# version_1.net
KiCad netlist of a schematic drawn in Altium Designer
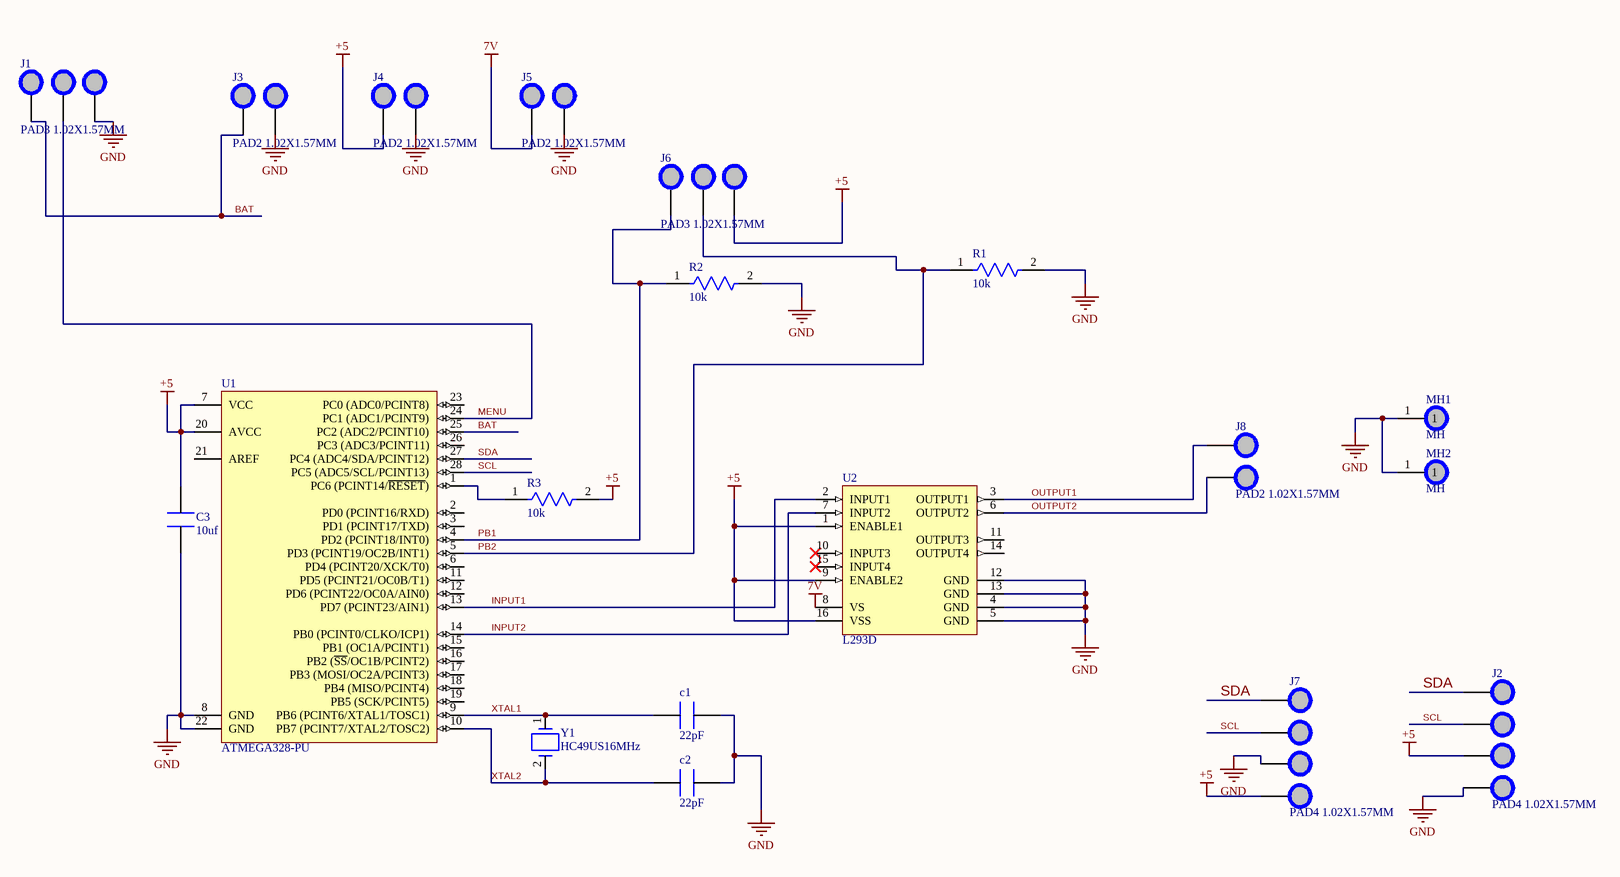
[diagram p0: version_1.SchDoc]

(export (version "E")
  (design (tool "Eeschema 10.0.6"))
  (components
    (comp (ref "c1")
      (value "22pF")
      (footprint "0805 22pf")
      (fields
        (field (name "MANUFACTURER") "KEMET")
        (field (name "MANUFACTURER PART NUMBER") "C0805C220J4HACTU")
      )
      (libsource (lib "Schlib1") (part "C0805C220J4HACTU"))
    )
    (comp (ref "c2")
      (value "22pF")
      (footprint "0805 22pf")
      (fields
        (field (name "MANUFACTURER") "KEMET")
        (field (name "MANUFACTURER PART NUMBER") "C0805C220J4HACTU")
      )
      (libsource (lib "Schlib1") (part "C0805C220J4HACTU"))
    )
    (comp (ref "C3")
      (value "10uf")
      (footprint "0805 cap")
      (fields
        (field (name "MANUFACTURER") "Samsung")
        (field (name "MANUFACTURER PART NUMBER") "CL21A106KOQNNNE")
        (field (name "TOLERANCE") "10%")
      )
      (libsource (lib "Schlib1") (part "CL21A106KOQNNNE"))
    )
    (comp (ref "J1")
      (value "PAD3 1.02X1.57MM")
      (footprint "PAD3 1.02X1.57MM")
      (libsource (lib "Schlib1") (part "PAD3 1.02X1.57MM"))
    )
    (comp (ref "J2")
      (value "PAD4 1.02X1.57MM")
      (footprint "PAD4 1.02X1.57MM")
      (libsource (lib "Schlib1") (part "PAD4 1.02X1.57MM"))
    )
    (comp (ref "J3")
      (value "PAD2 1.02X1.57MM")
      (footprint "PAD2 1.02X1.57MM")
      (libsource (lib "Schlib1") (part "PAD2 1.02X1.57MM"))
    )
    (comp (ref "J4")
      (value "PAD2 1.02X1.57MM")
      (footprint "PAD2 1.02X1.57MM")
      (libsource (lib "Schlib1") (part "PAD2 1.02X1.57MM"))
    )
    (comp (ref "J5")
      (value "PAD2 1.02X1.57MM")
      (footprint "PAD2 1.02X1.57MM")
      (libsource (lib "Schlib1") (part "PAD2 1.02X1.57MM"))
    )
    (comp (ref "J6")
      (value "PAD3 1.02X1.57MM")
      (footprint "PAD3 1.02X1.57MM")
      (libsource (lib "Schlib1") (part "PAD3 1.02X1.57MM"))
    )
    (comp (ref "J7")
      (value "PAD4 1.02X1.57MM")
      (footprint "PAD4 1.02X1.57MM")
      (libsource (lib "Schlib1") (part "PAD4 1.02X1.57MM"))
    )
    (comp (ref "J8")
      (value "PAD2 1.02X1.57MM")
      (footprint "PAD2 1.02X1.57MM")
      (libsource (lib "Schlib1") (part "PAD2 1.02X1.57MM"))
    )
    (comp (ref "MH1") (value "MH") (footprint "MH") (libsource (lib "Schlib1") (part "MH")))
    (comp (ref "MH2") (value "MH") (footprint "MH") (libsource (lib "Schlib1") (part "MH")))
    (comp (ref "R1")
      (value "10k")
      (footprint "0805 resistor")
      (description "Res Thick Film 0805 10K Ohm 1% 0.125W(1/8W) +/-100ppm/C Epoxy Pad SMD T/R")
      (fields
        (field (name "MANUFACTURER") "Yageo")
        (field (name "MANUFACTURER PART NUMBER") "RC0805FR-0710KL")
      )
      (libsource (lib "Schlib1") (part "RC0805FR-0710KL"))
    )
    (comp (ref "R2")
      (value "10k")
      (footprint "0805 resistor")
      (description "Res Thick Film 0805 10K Ohm 1% 0.125W(1/8W) +/-100ppm/C Epoxy Pad SMD T/R")
      (fields
        (field (name "MANUFACTURER") "Yageo")
        (field (name "MANUFACTURER PART NUMBER") "RC0805FR-0710KL")
      )
      (libsource (lib "Schlib1") (part "RC0805FR-0710KL"))
    )
    (comp (ref "R3")
      (value "10k")
      (footprint "0805 resistor")
      (description "Res Thick Film 0805 10K Ohm 1% 0.125W(1/8W) +/-100ppm/C Epoxy Pad SMD T/R")
      (fields
        (field (name "MANUFACTURER") "Yageo")
        (field (name "MANUFACTURER PART NUMBER") "RC0805FR-0710KL")
      )
      (libsource (lib "Schlib1") (part "RC0805FR-0710KL"))
    )
    (comp (ref "U1")
      (value "ATMEGA328-PU")
      (footprint "DIP28 7.62MM")
      (description "ATmega Series 32 kB Flash 2 kB SRAM 20 MHz 8-Bit Microcontroller - DIP-28")
      (fields (field (name "MANUFACTURER") "Microchip"))
      (libsource (lib "Schlib1") (part "ATMEGA328-PU"))
    )
    (comp (ref "U2")
      (value "L293D")
      (footprint "DIP16")
      (description "IC MOTOR DRIVER PAR 16-DIP")
      (fields (field (name "MANUFACTURER") "STMicroelectronics"))
      (libsource (lib "Schlib1") (part "L293D"))
    )
    (comp (ref "Y1")
      (value "HC49US16MHz")
      (footprint "HC49US16MHz")
      (fields
        (field (name "MANUFACTURER") "Citizen")
        (field (name "MANUFACTURER PART NUMBER") "HC49US16.384MABJ-UB")
      )
      (libsource (lib "Schlib1") (part "HC49US16.384MABJ-UB"))
    )
  )
  (nets
    (net (code "1") (name "+5") (class "Default")
      (node (ref "C3") (pin "2") (pinfunction "2_2") (pintype "passive"))
      (node (ref "J2") (pin "3") (pinfunction "3_3") (pintype "passive"))
      (node (ref "J4") (pin "1") (pinfunction "1_1") (pintype "passive"))
      (node (ref "J6") (pin "3") (pinfunction "3_3") (pintype "passive"))
      (node (ref "J7") (pin "4") (pinfunction "4_4") (pintype "passive"))
      (node (ref "R3") (pin "2") (pinfunction "2_2") (pintype "passive"))
      (node (ref "U1") (pin "20") (pinfunction "AVCC_20") (pintype "power_in"))
      (node (ref "U1") (pin "7") (pinfunction "VCC_7") (pintype "power_in"))
      (node (ref "U2") (pin "1") (pinfunction "ENABLE1_1") (pintype "input"))
      (node (ref "U2") (pin "16") (pinfunction "VSS_16") (pintype "passive"))
      (node (ref "U2") (pin "9") (pinfunction "ENABLE2_9") (pintype "input"))
    )
    (net (code "2") (name "/BAT") (class "Default")
      (node (ref "J1") (pin "1") (pinfunction "1_1") (pintype "passive"))
      (node (ref "J3") (pin "1") (pinfunction "1_1") (pintype "passive"))
      (node (ref "U1") (pin "25") (pinfunction "PC2_(ADC2/PCINT10)_25") (pintype "bidirectional"))
    )
    (net (code "3") (name "/INPUT1") (class "Default")
      (node (ref "U1") (pin "13") (pinfunction "PD7_(PCINT23/AIN1)_13") (pintype "bidirectional"))
      (node (ref "U2") (pin "2") (pinfunction "INPUT1_2") (pintype "input"))
    )
    (net (code "4") (name "/INPUT2") (class "Default")
      (node (ref "U1") (pin "14") (pinfunction "PB0_(PCINT0/CLKO/ICP1)_14") (pintype "bidirectional"))
      (node (ref "U2") (pin "7") (pinfunction "INPUT2_7") (pintype "input"))
    )
    (net (code "5") (name "/MENU") (class "Default")
      (node (ref "J1") (pin "2") (pinfunction "2_2") (pintype "passive"))
      (node (ref "U1") (pin "24") (pinfunction "PC1_(ADC1/PCINT9)_24") (pintype "bidirectional"))
    )
    (net (code "6") (name "/OUTPUT1") (class "Default")
      (node (ref "J8") (pin "1") (pinfunction "1_1") (pintype "passive"))
      (node (ref "U2") (pin "3") (pinfunction "OUTPUT1_3") (pintype "output"))
    )
    (net (code "7") (name "/OUTPUT2") (class "Default")
      (node (ref "J8") (pin "2") (pinfunction "2_2") (pintype "passive"))
      (node (ref "U2") (pin "6") (pinfunction "OUTPUT2_6") (pintype "output"))
    )
    (net (code "8") (name "/PB1") (class "Default")
      (node (ref "J6") (pin "1") (pinfunction "1_1") (pintype "passive"))
      (node (ref "R2") (pin "1") (pinfunction "1_1") (pintype "passive"))
      (node (ref "U1") (pin "4") (pinfunction "PD2_(PCINT18/INT0)_4") (pintype "bidirectional"))
    )
    (net (code "9") (name "/PB2") (class "Default")
      (node (ref "J6") (pin "2") (pinfunction "2_2") (pintype "passive"))
      (node (ref "R1") (pin "1") (pinfunction "1_1") (pintype "passive"))
      (node (ref "U1") (pin "5") (pinfunction "PD3_(PCINT19/OC2B/INT1)_5") (pintype "bidirectional"))
    )
    (net (code "10") (name "/SCL") (class "Default")
      (node (ref "J2") (pin "2") (pinfunction "2_2") (pintype "passive"))
      (node (ref "J7") (pin "2") (pinfunction "2_2") (pintype "passive"))
      (node (ref "U1") (pin "28") (pinfunction "PC5_(ADC5/SCL/PCINT13)_28") (pintype "bidirectional"))
    )
    (net (code "11") (name "/SDA") (class "Default")
      (node (ref "J2") (pin "1") (pinfunction "1_1") (pintype "passive"))
      (node (ref "J7") (pin "1") (pinfunction "1_1") (pintype "passive"))
      (node (ref "U1") (pin "27") (pinfunction "PC4_(ADC4/SDA/PCINT12)_27") (pintype "bidirectional"))
    )
    (net (code "12") (name "/XTAL1") (class "Default")
      (node (ref "U1") (pin "9") (pinfunction "PB6_(PCINT6/XTAL1/TOSC1)_9") (pintype "bidirectional"))
      (node (ref "Y1") (pin "1") (pinfunction "1_1") (pintype "passive"))
      (node (ref "c1") (pin "1") (pinfunction "1_1") (pintype "passive"))
    )
    (net (code "13") (name "/XTAL2") (class "Default")
      (node (ref "U1") (pin "10") (pinfunction "PB7_(PCINT7/XTAL2/TOSC2)_10") (pintype "bidirectional"))
      (node (ref "Y1") (pin "2") (pinfunction "2_2") (pintype "passive"))
      (node (ref "c2") (pin "1") (pinfunction "1_1") (pintype "passive"))
    )
    (net (code "14") (name "7V") (class "Default")
      (node (ref "J5") (pin "1") (pinfunction "1_1") (pintype "passive"))
      (node (ref "U2") (pin "8") (pinfunction "VS_8") (pintype "passive"))
    )
    (net (code "15") (name "GND") (class "Default")
      (node (ref "C3") (pin "1") (pinfunction "1_1") (pintype "passive"))
      (node (ref "J1") (pin "3") (pinfunction "3_3") (pintype "passive"))
      (node (ref "J2") (pin "4") (pinfunction "4_4") (pintype "passive"))
      (node (ref "J3") (pin "2") (pinfunction "2_2") (pintype "passive"))
      (node (ref "J4") (pin "2") (pinfunction "2_2") (pintype "passive"))
      (node (ref "J5") (pin "2") (pinfunction "2_2") (pintype "passive"))
      (node (ref "J7") (pin "3") (pinfunction "3_3") (pintype "passive"))
      (node (ref "MH1") (pin "1") (pinfunction "1_1") (pintype "passive"))
      (node (ref "MH2") (pin "1") (pinfunction "1_1") (pintype "passive"))
      (node (ref "R1") (pin "2") (pinfunction "2_2") (pintype "passive"))
      (node (ref "R2") (pin "2") (pinfunction "2_2") (pintype "passive"))
      (node (ref "U1") (pin "22") (pinfunction "GND_22") (pintype "power_in"))
      (node (ref "U1") (pin "8") (pinfunction "GND_8") (pintype "power_in"))
      (node (ref "U2") (pin "12") (pinfunction "GND_12") (pintype "passive"))
      (node (ref "U2") (pin "13") (pinfunction "GND_13") (pintype "passive"))
      (node (ref "U2") (pin "4") (pinfunction "GND_4") (pintype "passive"))
      (node (ref "U2") (pin "5") (pinfunction "GND_5") (pintype "passive"))
      (node (ref "c1") (pin "2") (pinfunction "2_2") (pintype "passive"))
      (node (ref "c2") (pin "2") (pinfunction "2_2") (pintype "passive"))
    )
    (net (code "16") (name "Net-(U1-PC6_(PCINT14{slash}~{RESET}))") (class "Default")
      (node (ref "R3") (pin "1") (pinfunction "1_1") (pintype "passive"))
      (node (ref "U1") (pin "1") (pinfunction "PC6_(PCINT14/~{RESET})_1") (pintype "bidirectional"))
    )
    (net (code "17") (name "unconnected-(U1-AREF-Pad21)") (class "Default")
      (node (ref "U1") (pin "21") (pinfunction "AREF_21") (pintype "power_in"))
    )
    (net (code "18") (name "unconnected-(U1-PB1_(OC1A{slash}PCINT1)-Pad15)") (class "Default")
      (node (ref "U1") (pin "15") (pinfunction "PB1_(OC1A/PCINT1)_15") (pintype "bidirectional"))
    )
    (net (code "19") (name "unconnected-(U1-PB2_(~{SS}{slash}OC1B{slash}PCINT2)-Pad16)") (class "Default")
      (node (ref "U1") (pin "16") (pinfunction "PB2_(~{SS}/OC1B/PCINT2)_16") (pintype "bidirectional"))
    )
    (net (code "20") (name "unconnected-(U1-PB3_(MOSI{slash}OC2A{slash}PCINT3)-Pad17)") (class "Default")
      (node (ref "U1") (pin "17") (pinfunction "PB3_(MOSI/OC2A/PCINT3)_17") (pintype "bidirectional"))
    )
    (net (code "21") (name "unconnected-(U1-PB4_(MISO{slash}PCINT4)-Pad18)") (class "Default")
      (node (ref "U1") (pin "18") (pinfunction "PB4_(MISO/PCINT4)_18") (pintype "bidirectional"))
    )
    (net (code "22") (name "unconnected-(U1-PB5_(SCK{slash}PCINT5)-Pad19)") (class "Default")
      (node (ref "U1") (pin "19") (pinfunction "PB5_(SCK/PCINT5)_19") (pintype "bidirectional"))
    )
    (net (code "23") (name "unconnected-(U1-PC0_(ADC0{slash}PCINT8)-Pad23)") (class "Default")
      (node (ref "U1") (pin "23") (pinfunction "PC0_(ADC0/PCINT8)_23") (pintype "bidirectional"))
    )
    (net (code "24") (name "unconnected-(U1-PC3_(ADC3{slash}PCINT11)-Pad26)") (class "Default")
      (node (ref "U1") (pin "26") (pinfunction "PC3_(ADC3/PCINT11)_26") (pintype "bidirectional"))
    )
    (net (code "25") (name "unconnected-(U1-PD0_(PCINT16{slash}RXD)-Pad2)") (class "Default")
      (node (ref "U1") (pin "2") (pinfunction "PD0_(PCINT16/RXD)_2") (pintype "bidirectional"))
    )
    (net (code "26") (name "unconnected-(U1-PD1_(PCINT17{slash}TXD)-Pad3)") (class "Default")
      (node (ref "U1") (pin "3") (pinfunction "PD1_(PCINT17/TXD)_3") (pintype "bidirectional"))
    )
    (net (code "27") (name "unconnected-(U1-PD4_(PCINT20{slash}XCK{slash}T0)-Pad6)") (class "Default")
      (node (ref "U1") (pin "6") (pinfunction "PD4_(PCINT20/XCK/T0)_6") (pintype "bidirectional"))
    )
    (net (code "28") (name "unconnected-(U1-PD5_(PCINT21{slash}OC0B{slash}T1)-Pad11)") (class "Default")
      (node (ref "U1") (pin "11") (pinfunction "PD5_(PCINT21/OC0B/T1)_11") (pintype "bidirectional"))
    )
    (net (code "29") (name "unconnected-(U1-PD6_(PCINT22{slash}OC0A{slash}AIN0)-Pad12)") (class "Default")
      (node (ref "U1") (pin "12") (pinfunction "PD6_(PCINT22/OC0A/AIN0)_12") (pintype "bidirectional"))
    )
    (net (code "30") (name "unconnected-(U2-INPUT3-Pad10)") (class "Default")
      (node (ref "U2") (pin "10") (pinfunction "INPUT3_10") (pintype "input+no_connect"))
    )
    (net (code "31") (name "unconnected-(U2-INPUT4-Pad15)") (class "Default")
      (node (ref "U2") (pin "15") (pinfunction "INPUT4_15") (pintype "input+no_connect"))
    )
    (net (code "32") (name "unconnected-(U2-OUTPUT3-Pad11)") (class "Default")
      (node (ref "U2") (pin "11") (pinfunction "OUTPUT3_11") (pintype "output"))
    )
    (net (code "33") (name "unconnected-(U2-OUTPUT4-Pad14)") (class "Default")
      (node (ref "U2") (pin "14") (pinfunction "OUTPUT4_14") (pintype "output"))
    )
  )
)
